# SCH_Rpi.net
KiCad netlist of a schematic drawn in EasyEDA
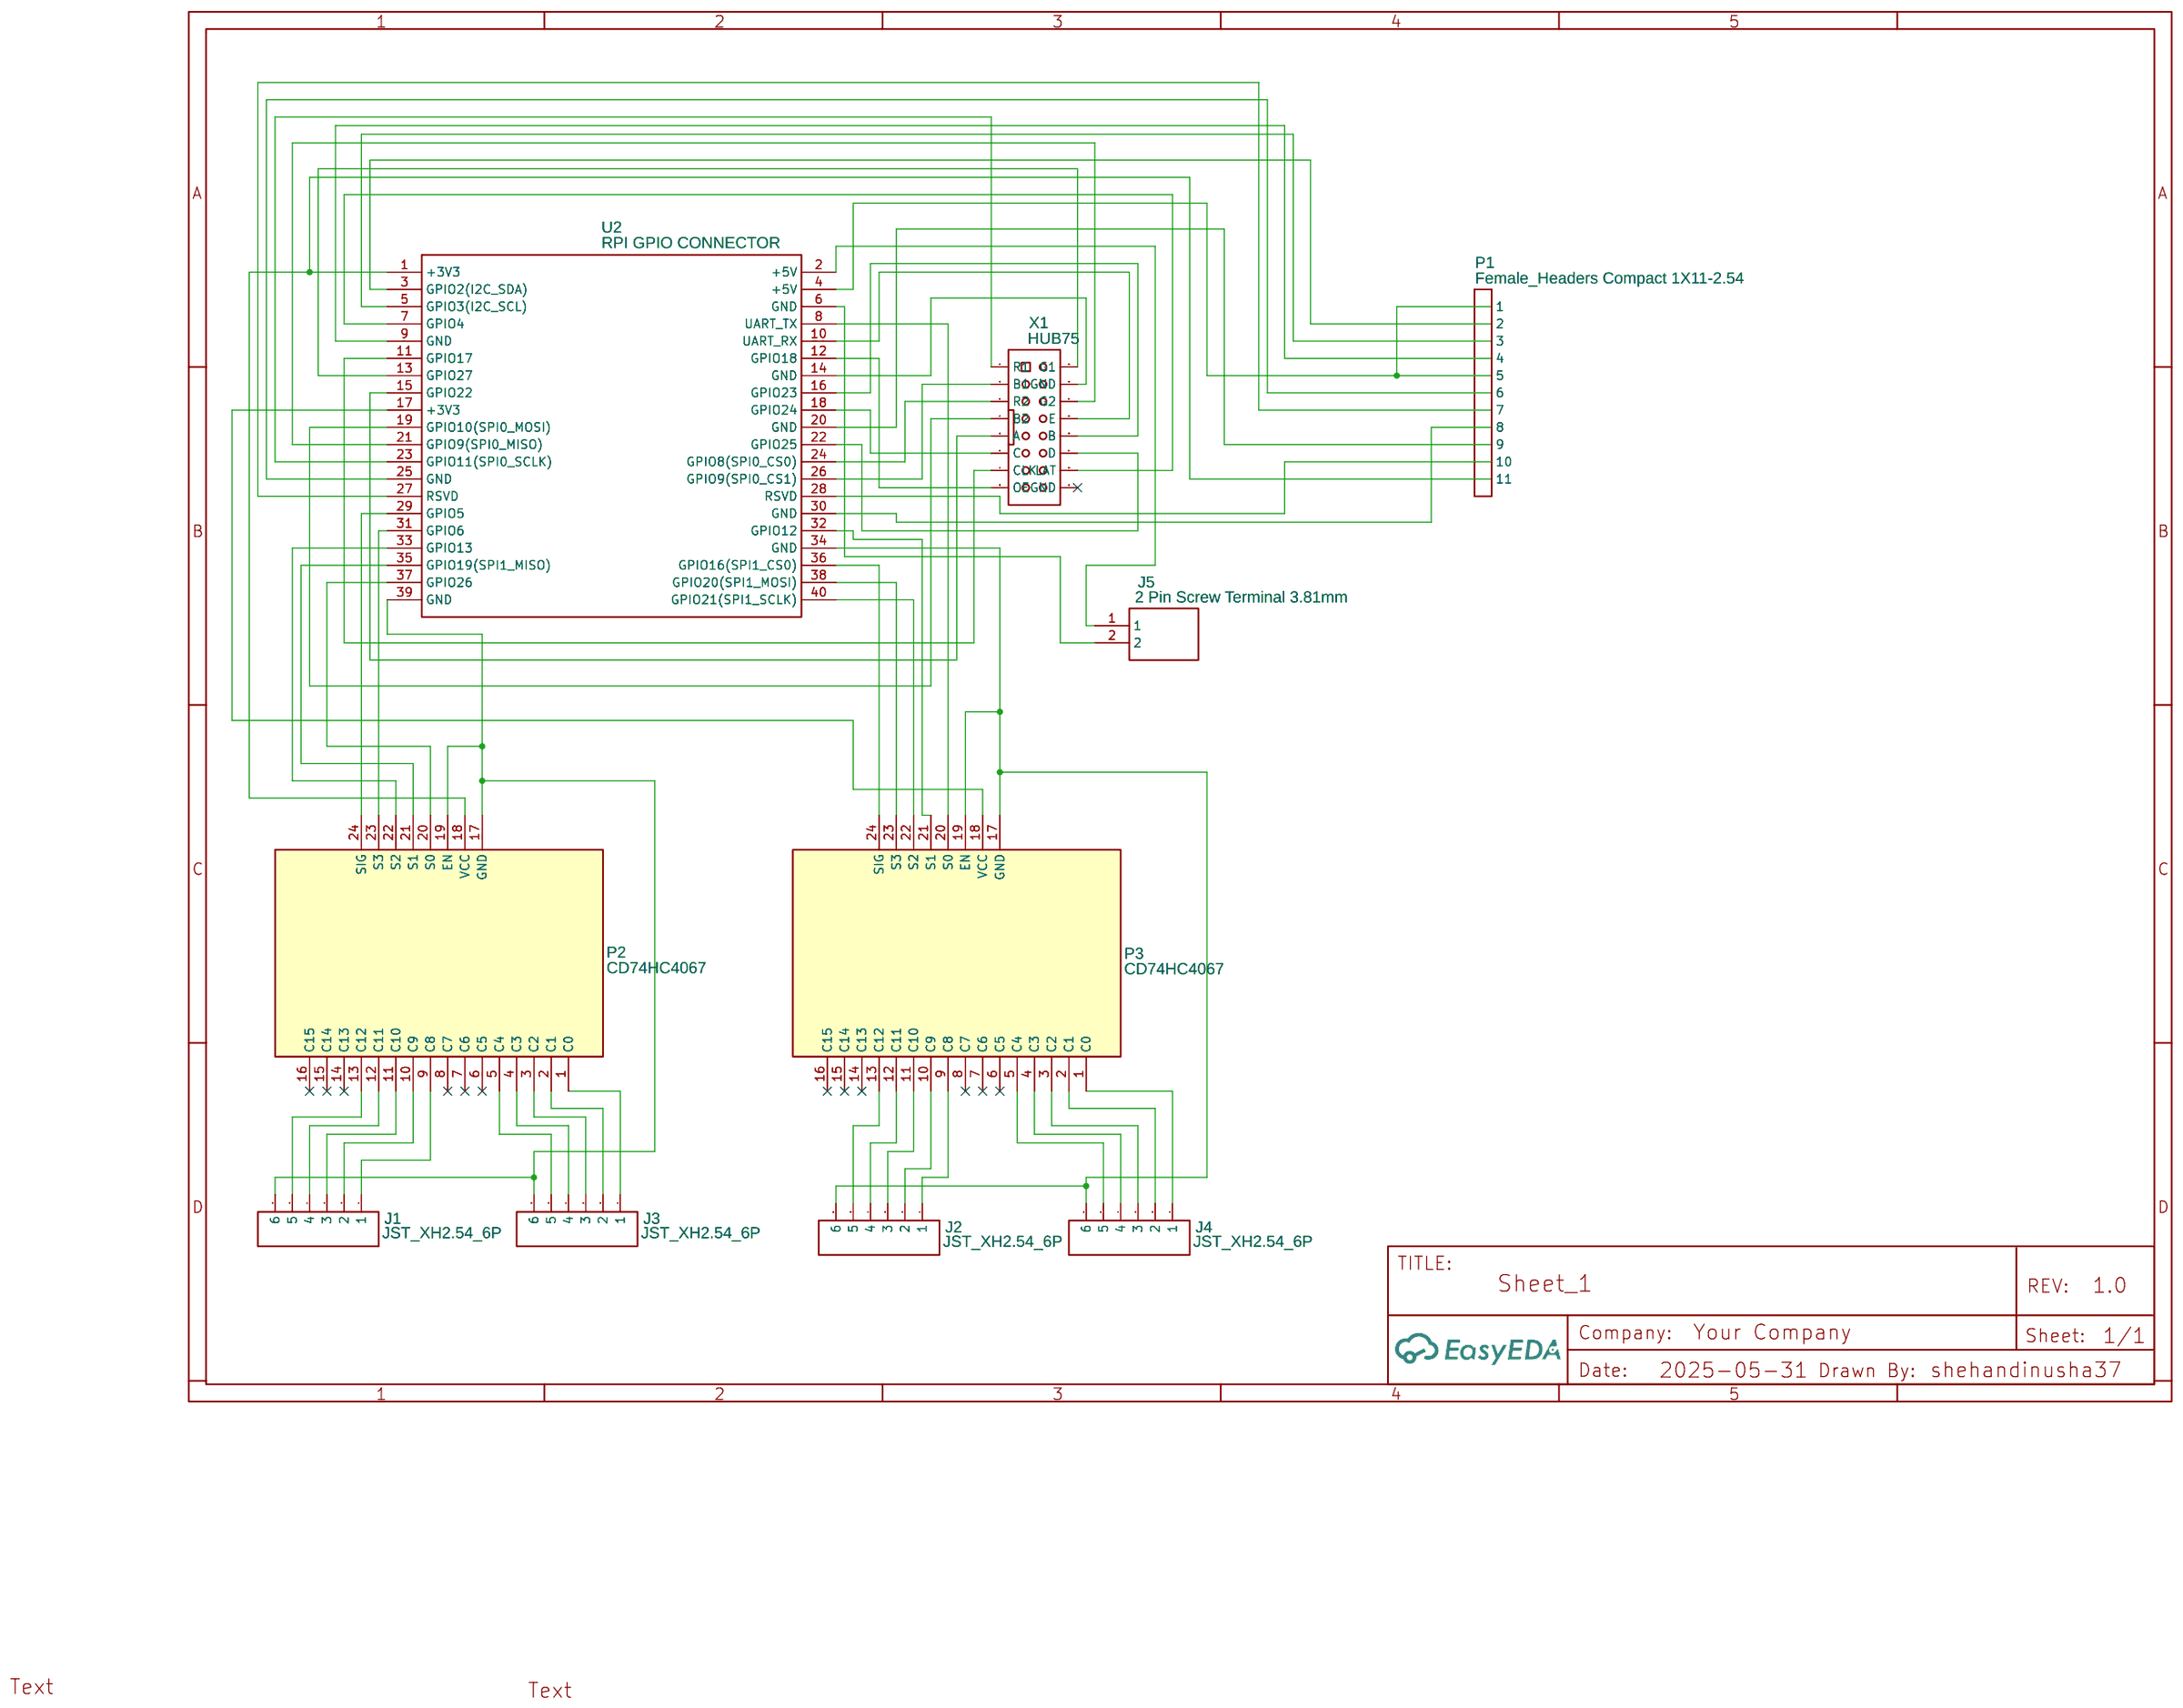
[diagram p0: schematic sheet]

(export (version "E")
  (design (tool "Eeschema 10.0.6"))
  (components
    (comp (ref "J1") (value "JST_XH2.54_6P") (libsource (lib "") (part "JST_XH2.54_6P")))
    (comp (ref "J2") (value "JST_XH2.54_6P") (libsource (lib "") (part "JST_XH2.54_6P")))
    (comp (ref "J3") (value "JST_XH2.54_6P") (libsource (lib "") (part "JST_XH2.54_6P")))
    (comp (ref "J4") (value "JST_XH2.54_6P") (libsource (lib "") (part "JST_XH2.54_6P")))
    (comp (ref "J5")
      (value "2 Pin Screw Terminal 3.81mm")
      (libsource (lib "") (part "2 Pin Screw Terminal 3.81mm"))
    )
    (comp (ref "P1")
      (value "Female_Headers Compact 1X11-2.54")
      (fields (field (name "Manufacturer Part") "Female Headers 1X11-2.54"))
      (libsource (lib "") (part "Female_Headers Compact 1X11-2.54"))
    )
    (comp (ref "P2") (value "CD74HC4067") (libsource (lib "") (part "CD74HC4067_1")))
    (comp (ref "P3") (value "CD74HC4067") (libsource (lib "") (part "CD74HC4067")))
    (comp (ref "U2")
      (value "RPI GPIO CONNECTOR")
      (fields (field (name "Manufacturer Part") "2.54-2*20") (field (name "Manufacturer") "ZHOURI(洲日)"))
      (libsource (lib "") (part "RPI GPIO CONNECTOR"))
    )
    (comp (ref "X1") (value "HUB75") (libsource (lib "") (part "HUB75")))
  )
  (nets
    (net (code "1") (name "Net-(J5-Pad1)") (class "Default")
      (node (ref "J5") (pin "1") (pinfunction "1_1") (pintype "unspecified"))
      (node (ref "U2") (pin "2") (pinfunction "+5V_2") (pintype "unspecified"))
    )
    (net (code "2") (name "Net-(J5-Pad2)") (class "Default")
      (node (ref "J5") (pin "2") (pinfunction "2_2") (pintype "unspecified"))
      (node (ref "U2") (pin "6") (pinfunction "GND_6") (pintype "unspecified"))
    )
    (net (code "3") (name "Net-(P1-Pad1)") (class "Default")
      (node (ref "P1") (pin "1") (pinfunction "1_1") (pintype "unspecified"))
      (node (ref "P1") (pin "5") (pinfunction "5_5") (pintype "unspecified"))
      (node (ref "U2") (pin "4") (pinfunction "+5V_4") (pintype "unspecified"))
    )
    (net (code "4") (name "Net-(P1-Pad4)") (class "Default")
      (node (ref "P1") (pin "4") (pinfunction "4_4") (pintype "unspecified"))
      (node (ref "U2") (pin "9") (pinfunction "GND_9") (pintype "unspecified"))
    )
    (net (code "5") (name "Net-(P1-Pad6)") (class "Default")
      (node (ref "P1") (pin "6") (pinfunction "6_6") (pintype "unspecified"))
      (node (ref "U2") (pin "25") (pinfunction "GND_25") (pintype "unspecified"))
    )
    (net (code "6") (name "Net-(P1-Pad7)") (class "Default")
      (node (ref "P1") (pin "7") (pinfunction "7_7") (pintype "unspecified"))
      (node (ref "U2") (pin "27") (pinfunction "RSVD_27") (pintype "unspecified"))
    )
    (net (code "7") (name "Net-(P1-Pad8)") (class "Default")
      (node (ref "P1") (pin "8") (pinfunction "8_8") (pintype "unspecified"))
      (node (ref "U2") (pin "30") (pinfunction "GND_30") (pintype "unspecified"))
    )
    (net (code "8") (name "Net-(P1-Pad9)") (class "Default")
      (node (ref "P1") (pin "9") (pinfunction "9_9") (pintype "unspecified"))
      (node (ref "U2") (pin "20") (pinfunction "GND_20") (pintype "unspecified"))
    )
    (net (code "9") (name "Net-(P1-Pad10)") (class "Default")
      (node (ref "P1") (pin "10") (pinfunction "10_10") (pintype "unspecified"))
      (node (ref "U2") (pin "28") (pinfunction "RSVD_28") (pintype "unspecified"))
    )
    (net (code "10") (name "Net-(P2-C0)") (class "Default")
      (node (ref "J3") (pin "1") (pinfunction "1_1") (pintype "unspecified"))
      (node (ref "P2") (pin "1") (pinfunction "C0_1") (pintype "unspecified"))
    )
    (net (code "11") (name "Net-(P2-C1)") (class "Default")
      (node (ref "J3") (pin "2") (pinfunction "2_2") (pintype "unspecified"))
      (node (ref "P2") (pin "2") (pinfunction "C1_2") (pintype "unspecified"))
    )
    (net (code "12") (name "Net-(P2-C2)") (class "Default")
      (node (ref "J3") (pin "3") (pinfunction "3_3") (pintype "unspecified"))
      (node (ref "P2") (pin "3") (pinfunction "C2_3") (pintype "unspecified"))
    )
    (net (code "13") (name "Net-(P2-C3)") (class "Default")
      (node (ref "J3") (pin "4") (pinfunction "4_4") (pintype "unspecified"))
      (node (ref "P2") (pin "4") (pinfunction "C3_4") (pintype "unspecified"))
    )
    (net (code "14") (name "Net-(P2-C4)") (class "Default")
      (node (ref "J3") (pin "5") (pinfunction "5_5") (pintype "unspecified"))
      (node (ref "P2") (pin "5") (pinfunction "C4_5") (pintype "unspecified"))
    )
    (net (code "15") (name "Net-(P2-C8)") (class "Default")
      (node (ref "J1") (pin "1") (pinfunction "1_1") (pintype "unspecified"))
      (node (ref "P2") (pin "9") (pinfunction "C8_9") (pintype "unspecified"))
    )
    (net (code "16") (name "Net-(P2-C9)") (class "Default")
      (node (ref "J1") (pin "2") (pinfunction "2_2") (pintype "unspecified"))
      (node (ref "P2") (pin "10") (pinfunction "C9_10") (pintype "unspecified"))
    )
    (net (code "17") (name "Net-(P2-C10)") (class "Default")
      (node (ref "J1") (pin "3") (pinfunction "3_3") (pintype "unspecified"))
      (node (ref "P2") (pin "11") (pinfunction "C10_11") (pintype "unspecified"))
    )
    (net (code "18") (name "Net-(P2-C11)") (class "Default")
      (node (ref "J1") (pin "4") (pinfunction "4_4") (pintype "unspecified"))
      (node (ref "P2") (pin "12") (pinfunction "C11_12") (pintype "unspecified"))
    )
    (net (code "19") (name "Net-(P2-C12)") (class "Default")
      (node (ref "J1") (pin "5") (pinfunction "5_5") (pintype "unspecified"))
      (node (ref "P2") (pin "13") (pinfunction "C12_13") (pintype "unspecified"))
    )
    (net (code "20") (name "Net-(P2-EN)") (class "Default")
      (node (ref "J1") (pin "6") (pinfunction "6_6") (pintype "unspecified"))
      (node (ref "J3") (pin "6") (pinfunction "6_6") (pintype "unspecified"))
      (node (ref "P2") (pin "17") (pinfunction "GND_17") (pintype "unspecified"))
      (node (ref "P2") (pin "19") (pinfunction "EN_19") (pintype "unspecified"))
      (node (ref "U2") (pin "39") (pinfunction "GND_39") (pintype "unspecified"))
    )
    (net (code "21") (name "Net-(P2-S0)") (class "Default")
      (node (ref "P2") (pin "20") (pinfunction "S0_20") (pintype "unspecified"))
      (node (ref "U2") (pin "37") (pinfunction "GPIO26_37") (pintype "unspecified"))
    )
    (net (code "22") (name "Net-(P2-S1)") (class "Default")
      (node (ref "P2") (pin "21") (pinfunction "S1_21") (pintype "unspecified"))
      (node (ref "U2") (pin "35") (pinfunction "GPIO19(SPI1_MISO)_35") (pintype "unspecified"))
    )
    (net (code "23") (name "Net-(P2-S2)") (class "Default")
      (node (ref "P2") (pin "22") (pinfunction "S2_22") (pintype "unspecified"))
      (node (ref "U2") (pin "33") (pinfunction "GPIO13_33") (pintype "unspecified"))
    )
    (net (code "24") (name "Net-(P2-S3)") (class "Default")
      (node (ref "P2") (pin "23") (pinfunction "S3_23") (pintype "unspecified"))
      (node (ref "U2") (pin "31") (pinfunction "GPIO6_31") (pintype "unspecified"))
    )
    (net (code "25") (name "Net-(P2-SIG)") (class "Default")
      (node (ref "P2") (pin "24") (pinfunction "SIG_24") (pintype "unspecified"))
      (node (ref "U2") (pin "29") (pinfunction "GPIO5_29") (pintype "unspecified"))
    )
    (net (code "26") (name "Net-(P2-VCC)") (class "Default")
      (node (ref "P1") (pin "11") (pinfunction "11_11") (pintype "unspecified"))
      (node (ref "P2") (pin "18") (pinfunction "VCC_18") (pintype "unspecified"))
      (node (ref "U2") (pin "1") (pinfunction "+3V3_1") (pintype "unspecified"))
    )
    (net (code "27") (name "Net-(P3-C0)") (class "Default")
      (node (ref "J4") (pin "1") (pinfunction "1_1") (pintype "unspecified"))
      (node (ref "P3") (pin "1") (pinfunction "C0_1") (pintype "unspecified"))
    )
    (net (code "28") (name "Net-(P3-C1)") (class "Default")
      (node (ref "J4") (pin "2") (pinfunction "2_2") (pintype "unspecified"))
      (node (ref "P3") (pin "2") (pinfunction "C1_2") (pintype "unspecified"))
    )
    (net (code "29") (name "Net-(P3-C2)") (class "Default")
      (node (ref "J4") (pin "3") (pinfunction "3_3") (pintype "unspecified"))
      (node (ref "P3") (pin "3") (pinfunction "C2_3") (pintype "unspecified"))
    )
    (net (code "30") (name "Net-(P3-C3)") (class "Default")
      (node (ref "J4") (pin "4") (pinfunction "4_4") (pintype "unspecified"))
      (node (ref "P3") (pin "4") (pinfunction "C3_4") (pintype "unspecified"))
    )
    (net (code "31") (name "Net-(P3-C4)") (class "Default")
      (node (ref "J4") (pin "5") (pinfunction "5_5") (pintype "unspecified"))
      (node (ref "P3") (pin "5") (pinfunction "C4_5") (pintype "unspecified"))
    )
    (net (code "32") (name "Net-(P3-C8)") (class "Default")
      (node (ref "J2") (pin "1") (pinfunction "1_1") (pintype "unspecified"))
      (node (ref "P3") (pin "9") (pinfunction "C8_9") (pintype "unspecified"))
    )
    (net (code "33") (name "Net-(P3-C9)") (class "Default")
      (node (ref "J2") (pin "2") (pinfunction "2_2") (pintype "unspecified"))
      (node (ref "P3") (pin "10") (pinfunction "C9_10") (pintype "unspecified"))
    )
    (net (code "34") (name "Net-(P3-C10)") (class "Default")
      (node (ref "J2") (pin "3") (pinfunction "3_3") (pintype "unspecified"))
      (node (ref "P3") (pin "11") (pinfunction "C10_11") (pintype "unspecified"))
    )
    (net (code "35") (name "Net-(P3-C11)") (class "Default")
      (node (ref "J2") (pin "4") (pinfunction "4_4") (pintype "unspecified"))
      (node (ref "P3") (pin "12") (pinfunction "C11_12") (pintype "unspecified"))
    )
    (net (code "36") (name "Net-(P3-C12)") (class "Default")
      (node (ref "J2") (pin "5") (pinfunction "5_5") (pintype "unspecified"))
      (node (ref "P3") (pin "13") (pinfunction "C12_13") (pintype "unspecified"))
    )
    (net (code "37") (name "Net-(P3-EN)") (class "Default")
      (node (ref "J2") (pin "6") (pinfunction "6_6") (pintype "unspecified"))
      (node (ref "J4") (pin "6") (pinfunction "6_6") (pintype "unspecified"))
      (node (ref "P3") (pin "17") (pinfunction "GND_17") (pintype "unspecified"))
      (node (ref "P3") (pin "19") (pinfunction "EN_19") (pintype "unspecified"))
      (node (ref "U2") (pin "34") (pinfunction "GND_34") (pintype "unspecified"))
    )
    (net (code "38") (name "Net-(P3-S0)") (class "Default")
      (node (ref "P3") (pin "20") (pinfunction "S0_20") (pintype "unspecified"))
      (node (ref "U2") (pin "8") (pinfunction "UART_TX_8") (pintype "unspecified"))
    )
    (net (code "39") (name "Net-(P3-S1)") (class "Default")
      (node (ref "P3") (pin "21") (pinfunction "S1_21") (pintype "unspecified"))
      (node (ref "U2") (pin "32") (pinfunction "GPIO12_32") (pintype "unspecified"))
    )
    (net (code "40") (name "Net-(P3-S2)") (class "Default")
      (node (ref "P3") (pin "22") (pinfunction "S2_22") (pintype "unspecified"))
      (node (ref "U2") (pin "40") (pinfunction "GPIO21(SPI1_SCLK)_40") (pintype "unspecified"))
    )
    (net (code "41") (name "Net-(P3-S3)") (class "Default")
      (node (ref "P3") (pin "23") (pinfunction "S3_23") (pintype "unspecified"))
      (node (ref "U2") (pin "38") (pinfunction "GPIO20(SPI1_MOSI)_38") (pintype "unspecified"))
    )
    (net (code "42") (name "Net-(P3-SIG)") (class "Default")
      (node (ref "P3") (pin "24") (pinfunction "SIG_24") (pintype "unspecified"))
      (node (ref "U2") (pin "36") (pinfunction "GPIO16(SPI1_CS0)_36") (pintype "unspecified"))
    )
    (net (code "43") (name "Net-(P3-VCC)") (class "Default")
      (node (ref "P3") (pin "18") (pinfunction "VCC_18") (pintype "unspecified"))
      (node (ref "U2") (pin "17") (pinfunction "+3V3_17") (pintype "unspecified"))
    )
    (net (code "44") (name "Net-(U2-GND-Pad14)") (class "Default")
      (node (ref "U2") (pin "14") (pinfunction "GND_14") (pintype "unspecified"))
      (node (ref "X1") (pin "15") (pinfunction "GND_15") (pintype "unspecified"))
    )
    (net (code "45") (name "Net-(U2-GPIO2(I2C_SDA))") (class "Default")
      (node (ref "P1") (pin "2") (pinfunction "2_2") (pintype "unspecified"))
      (node (ref "U2") (pin "3") (pinfunction "GPIO2(I2C_SDA)_3") (pintype "unspecified"))
    )
    (net (code "46") (name "Net-(U2-GPIO3(I2C_SCL))") (class "Default")
      (node (ref "P1") (pin "3") (pinfunction "3_3") (pintype "unspecified"))
      (node (ref "U2") (pin "5") (pinfunction "GPIO3(I2C_SCL)_5") (pintype "unspecified"))
    )
    (net (code "47") (name "Net-(U2-GPIO4)") (class "Default")
      (node (ref "U2") (pin "7") (pinfunction "GPIO4_7") (pintype "unspecified"))
      (node (ref "X1") (pin "10") (pinfunction "LAT_10") (pintype "unspecified"))
    )
    (net (code "48") (name "Net-(U2-GPIO8(SPI0_CS0))") (class "Default")
      (node (ref "U2") (pin "24") (pinfunction "GPIO8(SPI0_CS0)_24") (pintype "unspecified"))
      (node (ref "X1") (pin "3") (pinfunction "R2_3") (pintype "unspecified"))
    )
    (net (code "49") (name "Net-(U2-GPIO9(SPI0_CS1))") (class "Default")
      (node (ref "U2") (pin "26") (pinfunction "GPIO9(SPI0_CS1)_26") (pintype "unspecified"))
      (node (ref "X1") (pin "2") (pinfunction "B1_2") (pintype "unspecified"))
    )
    (net (code "50") (name "Net-(U2-GPIO9(SPI0_MISO))") (class "Default")
      (node (ref "U2") (pin "21") (pinfunction "GPIO9(SPI0_MISO)_21") (pintype "unspecified"))
      (node (ref "X1") (pin "14") (pinfunction "G2_14") (pintype "unspecified"))
    )
    (net (code "51") (name "Net-(U2-GPIO10(SPI0_MOSI))") (class "Default")
      (node (ref "U2") (pin "19") (pinfunction "GPIO10(SPI0_MOSI)_19") (pintype "unspecified"))
      (node (ref "X1") (pin "4") (pinfunction "B2_4") (pintype "unspecified"))
    )
    (net (code "52") (name "Net-(U2-GPIO11(SPI0_SCLK))") (class "Default")
      (node (ref "U2") (pin "23") (pinfunction "GPIO11(SPI0_SCLK)_23") (pintype "unspecified"))
      (node (ref "X1") (pin "1") (pinfunction "R1_1") (pintype "unspecified"))
    )
    (net (code "53") (name "Net-(U2-GPIO17)") (class "Default")
      (node (ref "U2") (pin "11") (pinfunction "GPIO17_11") (pintype "unspecified"))
      (node (ref "X1") (pin "7") (pinfunction "CLK_7") (pintype "unspecified"))
    )
    (net (code "54") (name "Net-(U2-GPIO18)") (class "Default")
      (node (ref "U2") (pin "12") (pinfunction "GPIO18_12") (pintype "unspecified"))
      (node (ref "X1") (pin "8") (pinfunction "OE_8") (pintype "unspecified"))
    )
    (net (code "55") (name "Net-(U2-GPIO22)") (class "Default")
      (node (ref "U2") (pin "15") (pinfunction "GPIO22_15") (pintype "unspecified"))
      (node (ref "X1") (pin "5") (pinfunction "A_5") (pintype "unspecified"))
    )
    (net (code "56") (name "Net-(U2-GPIO23)") (class "Default")
      (node (ref "U2") (pin "16") (pinfunction "GPIO23_16") (pintype "unspecified"))
      (node (ref "X1") (pin "12") (pinfunction "B_12") (pintype "unspecified"))
    )
    (net (code "57") (name "Net-(U2-GPIO24)") (class "Default")
      (node (ref "U2") (pin "18") (pinfunction "GPIO24_18") (pintype "unspecified"))
      (node (ref "X1") (pin "6") (pinfunction "C_6") (pintype "unspecified"))
    )
    (net (code "58") (name "Net-(U2-GPIO25)") (class "Default")
      (node (ref "U2") (pin "22") (pinfunction "GPIO25_22") (pintype "unspecified"))
      (node (ref "X1") (pin "11") (pinfunction "D_11") (pintype "unspecified"))
    )
    (net (code "59") (name "Net-(U2-GPIO27)") (class "Default")
      (node (ref "U2") (pin "13") (pinfunction "GPIO27_13") (pintype "unspecified"))
      (node (ref "X1") (pin "16") (pinfunction "G1_16") (pintype "unspecified"))
    )
    (net (code "60") (name "Net-(U2-UART_RX)") (class "Default")
      (node (ref "U2") (pin "10") (pinfunction "UART_RX_10") (pintype "unspecified"))
      (node (ref "X1") (pin "13") (pinfunction "E_13") (pintype "unspecified"))
    )
    (net (code "61") (name "unconnected-(P2-C5-Pad6)") (class "Default")
      (node (ref "P2") (pin "6") (pinfunction "C5_6") (pintype "unspecified+no_connect"))
    )
    (net (code "62") (name "unconnected-(P2-C6-Pad7)") (class "Default")
      (node (ref "P2") (pin "7") (pinfunction "C6_7") (pintype "unspecified+no_connect"))
    )
    (net (code "63") (name "unconnected-(P2-C7-Pad8)") (class "Default")
      (node (ref "P2") (pin "8") (pinfunction "C7_8") (pintype "unspecified+no_connect"))
    )
    (net (code "64") (name "unconnected-(P2-C13-Pad14)") (class "Default")
      (node (ref "P2") (pin "14") (pinfunction "C13_14") (pintype "unspecified+no_connect"))
    )
    (net (code "65") (name "unconnected-(P2-C14-Pad15)") (class "Default")
      (node (ref "P2") (pin "15") (pinfunction "C14_15") (pintype "unspecified+no_connect"))
    )
    (net (code "66") (name "unconnected-(P2-C15-Pad16)") (class "Default")
      (node (ref "P2") (pin "16") (pinfunction "C15_16") (pintype "unspecified+no_connect"))
    )
    (net (code "67") (name "unconnected-(P3-C5-Pad6)") (class "Default")
      (node (ref "P3") (pin "6") (pinfunction "C5_6") (pintype "unspecified+no_connect"))
    )
    (net (code "68") (name "unconnected-(P3-C6-Pad7)") (class "Default")
      (node (ref "P3") (pin "7") (pinfunction "C6_7") (pintype "unspecified+no_connect"))
    )
    (net (code "69") (name "unconnected-(P3-C7-Pad8)") (class "Default")
      (node (ref "P3") (pin "8") (pinfunction "C7_8") (pintype "unspecified+no_connect"))
    )
    (net (code "70") (name "unconnected-(P3-C13-Pad14)") (class "Default")
      (node (ref "P3") (pin "14") (pinfunction "C13_14") (pintype "unspecified+no_connect"))
    )
    (net (code "71") (name "unconnected-(P3-C14-Pad15)") (class "Default")
      (node (ref "P3") (pin "15") (pinfunction "C14_15") (pintype "unspecified+no_connect"))
    )
    (net (code "72") (name "unconnected-(P3-C15-Pad16)") (class "Default")
      (node (ref "P3") (pin "16") (pinfunction "C15_16") (pintype "unspecified+no_connect"))
    )
    (net (code "73") (name "unconnected-(X1-GND-Pad9)") (class "Default")
      (node (ref "X1") (pin "9") (pinfunction "GND_9") (pintype "unspecified+no_connect"))
    )
  )
)
